# NESv4.net
KiCad netlist of a schematic drawn in EAGLE
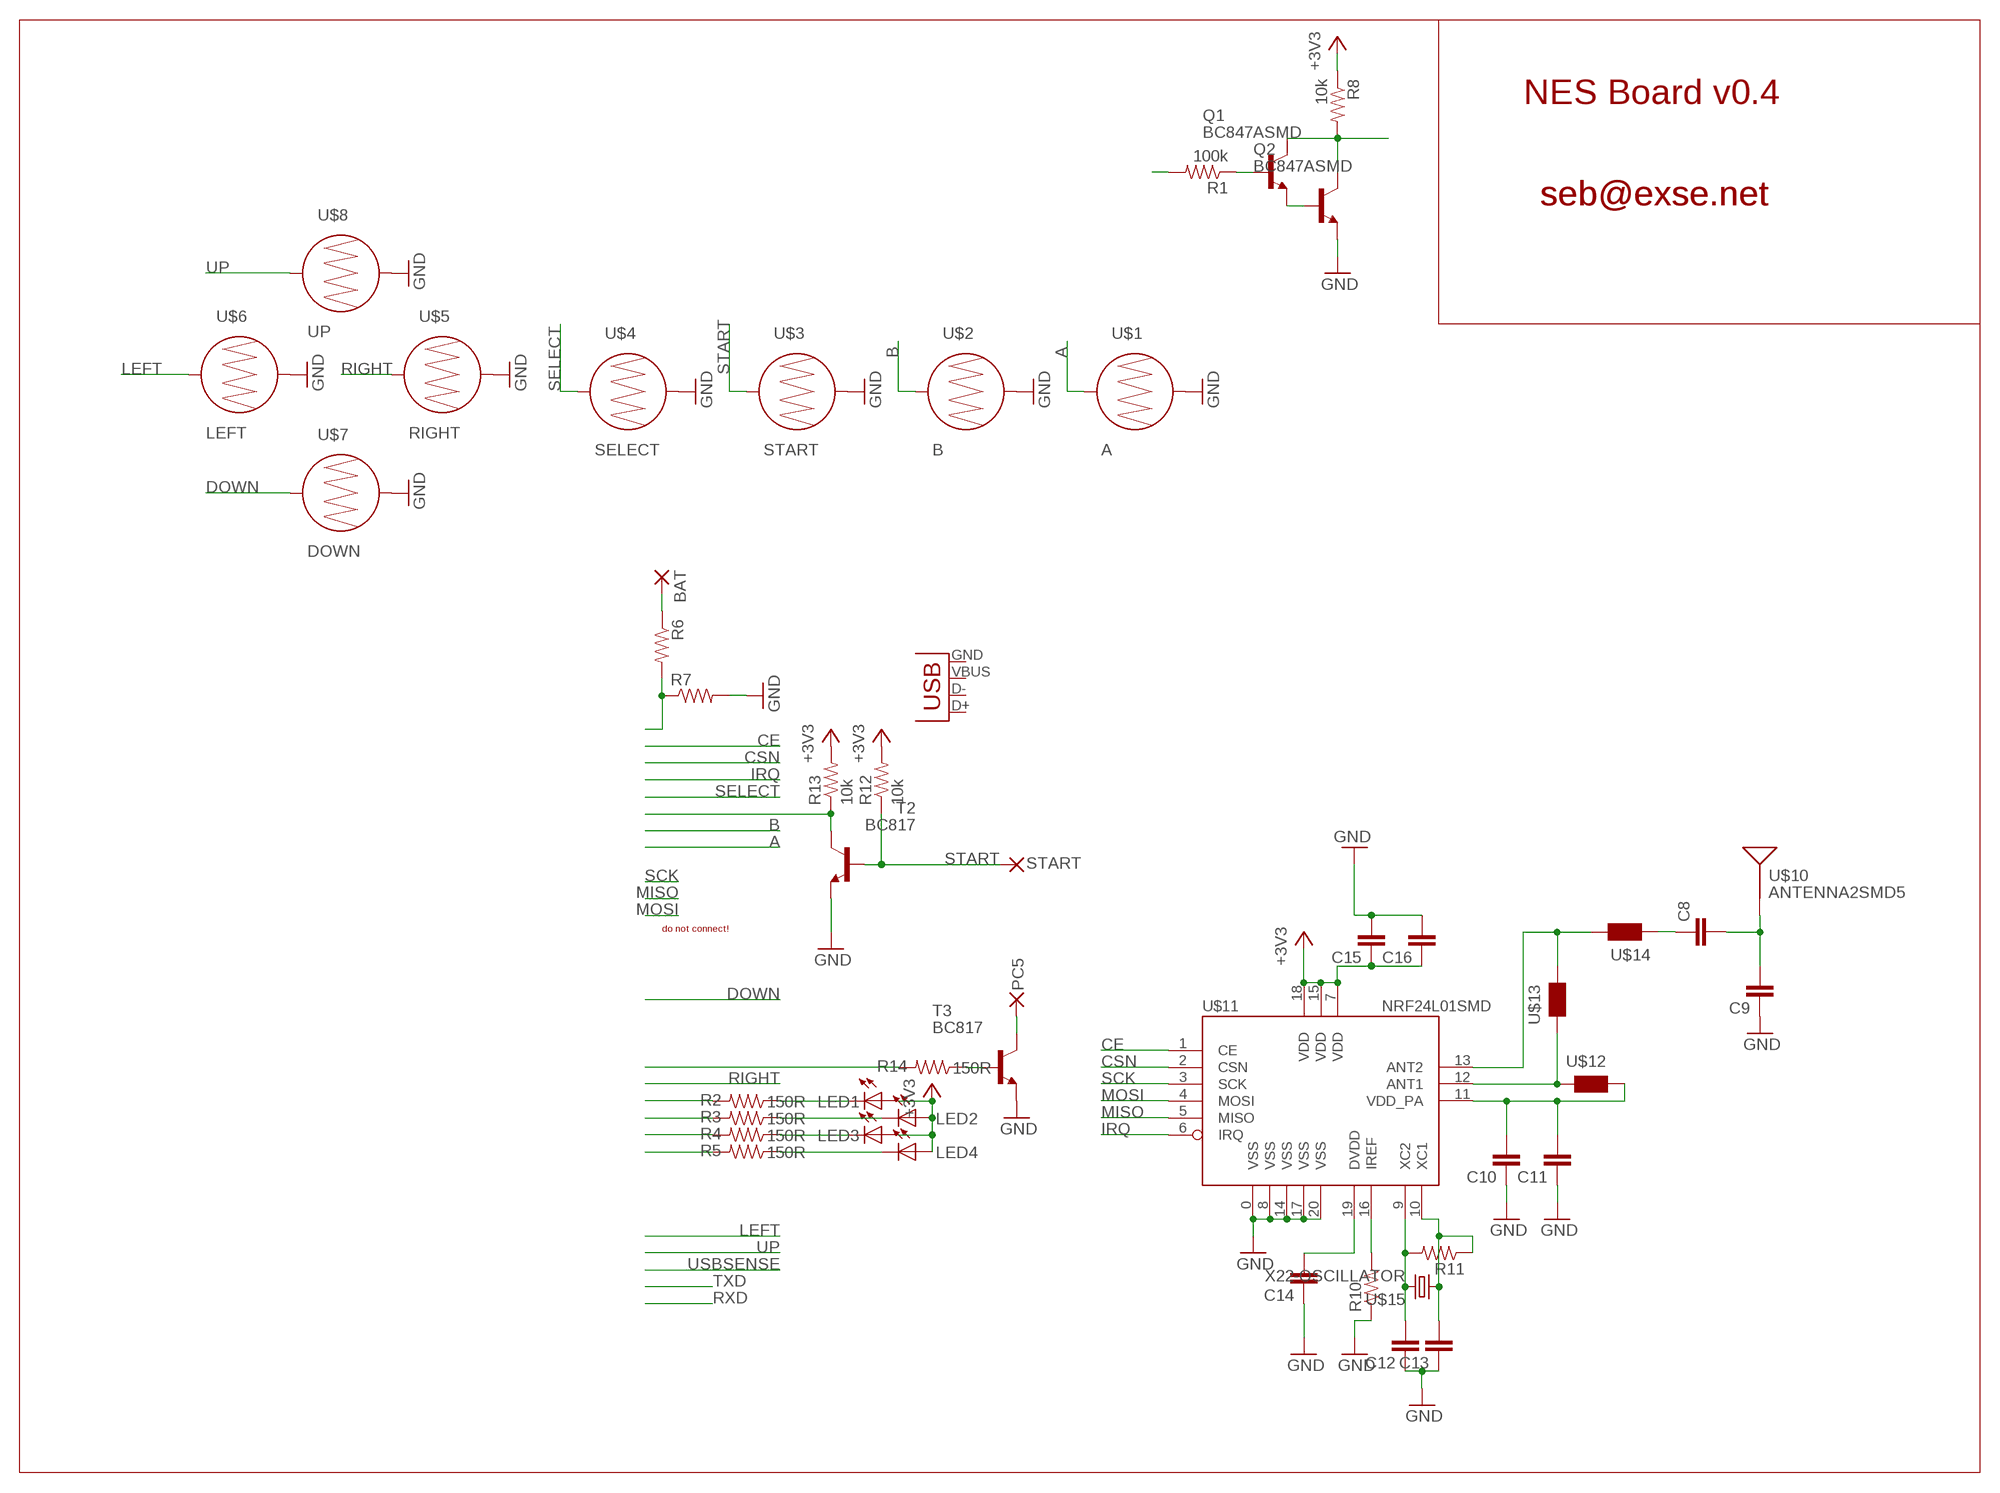
[diagram p0: schematic, sheet 1]

(export (version "E")
  (design (tool "Eeschema 10.0.6"))
  (components
    (comp (ref "BAT")
      (value "SMD2")
      (footprint "eagle-import:SMD1,27-2,54")
      (libsource (lib "eagle-import") (part "SMD2"))
    )
    (comp (ref "C8")
      (value "CAP0805")
      (footprint "eagle-import:0805")
      (libsource (lib "eagle-import") (part "CAP0805"))
    )
    (comp (ref "C9")
      (value "CAP0805")
      (footprint "eagle-import:0805")
      (libsource (lib "eagle-import") (part "CAP0805"))
    )
    (comp (ref "C10")
      (value "CAP0805")
      (footprint "eagle-import:0805")
      (libsource (lib "eagle-import") (part "CAP0805"))
    )
    (comp (ref "C11")
      (value "CAP0805")
      (footprint "eagle-import:0805")
      (libsource (lib "eagle-import") (part "CAP0805"))
    )
    (comp (ref "C12")
      (value "CAP0805")
      (footprint "eagle-import:0805")
      (libsource (lib "eagle-import") (part "CAP0805"))
    )
    (comp (ref "C13")
      (value "CAP0805")
      (footprint "eagle-import:0805")
      (libsource (lib "eagle-import") (part "CAP0805"))
    )
    (comp (ref "C14")
      (value "CAP0805")
      (footprint "eagle-import:0805")
      (libsource (lib "eagle-import") (part "CAP0805"))
    )
    (comp (ref "C15")
      (value "CAP0805")
      (footprint "eagle-import:0805")
      (libsource (lib "eagle-import") (part "CAP0805"))
    )
    (comp (ref "C16")
      (value "CAP0805")
      (footprint "eagle-import:0805")
      (libsource (lib "eagle-import") (part "CAP0805"))
    )
    (comp (ref "LED1")
      (value "LED3MM")
      (footprint "eagle-import:LED3MM")
      (libsource (lib "eagle-import") (part "LED3MM"))
    )
    (comp (ref "LED2")
      (value "LED3MM")
      (footprint "eagle-import:LED3MM")
      (libsource (lib "eagle-import") (part "LED3MM"))
    )
    (comp (ref "LED3")
      (value "LED3MM")
      (footprint "eagle-import:LED3MM")
      (libsource (lib "eagle-import") (part "LED3MM"))
    )
    (comp (ref "LED4")
      (value "LED3MM")
      (footprint "eagle-import:LED3MM")
      (libsource (lib "eagle-import") (part "LED3MM"))
    )
    (comp (ref "PC5")
      (value "SMD2")
      (footprint "eagle-import:SMD1,27-2,54")
      (libsource (lib "eagle-import") (part "SMD2"))
    )
    (comp (ref "Q1")
      (value "BC847ASMD")
      (footprint "eagle-import:SOT23")
      (libsource (lib "eagle-import") (part "BC847SMDA"))
    )
    (comp (ref "Q2")
      (value "BC847ASMD")
      (footprint "eagle-import:SOT23")
      (libsource (lib "eagle-import") (part "BC847SMDA"))
    )
    (comp (ref "R1")
      (value "100k")
      (footprint "eagle-import:0805")
      (libsource (lib "eagle-import") (part "RESISTOR"))
    )
    (comp (ref "R2")
      (value "150R")
      (footprint "eagle-import:0805")
      (libsource (lib "eagle-import") (part "RESISTOR"))
    )
    (comp (ref "R3")
      (value "150R")
      (footprint "eagle-import:0805")
      (libsource (lib "eagle-import") (part "RESISTOR"))
    )
    (comp (ref "R4")
      (value "150R")
      (footprint "eagle-import:0805")
      (libsource (lib "eagle-import") (part "RESISTOR"))
    )
    (comp (ref "R5")
      (value "150R")
      (footprint "eagle-import:0805")
      (libsource (lib "eagle-import") (part "RESISTOR"))
    )
    (comp (ref "R6")
      (value "RESISTOR")
      (footprint "eagle-import:0805")
      (libsource (lib "eagle-import") (part "RESISTOR"))
    )
    (comp (ref "R7")
      (value "RESISTOR")
      (footprint "eagle-import:0805")
      (libsource (lib "eagle-import") (part "RESISTOR"))
    )
    (comp (ref "R8")
      (value "10k")
      (footprint "eagle-import:0805")
      (libsource (lib "eagle-import") (part "RESISTOR"))
    )
    (comp (ref "R10")
      (value "RESISTOR")
      (footprint "eagle-import:0805")
      (libsource (lib "eagle-import") (part "RESISTOR"))
    )
    (comp (ref "R11")
      (value "RESISTOR")
      (footprint "eagle-import:0805")
      (libsource (lib "eagle-import") (part "RESISTOR"))
    )
    (comp (ref "R12")
      (value "10k")
      (footprint "eagle-import:0805")
      (libsource (lib "eagle-import") (part "RESISTOR"))
    )
    (comp (ref "R13")
      (value "10k")
      (footprint "eagle-import:0805")
      (libsource (lib "eagle-import") (part "RESISTOR"))
    )
    (comp (ref "R14")
      (value "150R")
      (footprint "eagle-import:0805")
      (libsource (lib "eagle-import") (part "RESISTOR"))
    )
    (comp (ref "START")
      (value "SMD2")
      (footprint "eagle-import:SMD1,27-2,54")
      (libsource (lib "eagle-import") (part "SMD2"))
    )
    (comp (ref "T2")
      (value "BC817")
      (footprint "eagle-import:SOT23")
      (libsource (lib "eagle-import") (part "BC847"))
    )
    (comp (ref "T3")
      (value "BC817")
      (footprint "eagle-import:SOT23")
      (libsource (lib "eagle-import") (part "BC847"))
    )
    (comp (ref "U$1")
      (value "A")
      (footprint "eagle-import:BUTTON-CONDUCTIVE")
      (libsource (lib "eagle-import") (part "BUTTON-CONDUCTIVESMD"))
    )
    (comp (ref "U$2")
      (value "B")
      (footprint "eagle-import:BUTTON-CONDUCTIVE")
      (libsource (lib "eagle-import") (part "BUTTON-CONDUCTIVESMD"))
    )
    (comp (ref "U$3")
      (value "START")
      (footprint "eagle-import:BUTTON-CONDUCTIVE")
      (libsource (lib "eagle-import") (part "BUTTON-CONDUCTIVESMD"))
    )
    (comp (ref "U$4")
      (value "SELECT")
      (footprint "eagle-import:BUTTON-CONDUCTIVE")
      (libsource (lib "eagle-import") (part "BUTTON-CONDUCTIVESMD"))
    )
    (comp (ref "U$5")
      (value "RIGHT")
      (footprint "eagle-import:BUTTON-CONDUCTIVE")
      (libsource (lib "eagle-import") (part "BUTTON-CONDUCTIVESMD"))
    )
    (comp (ref "U$6")
      (value "LEFT")
      (footprint "eagle-import:BUTTON-CONDUCTIVE")
      (libsource (lib "eagle-import") (part "BUTTON-CONDUCTIVESMD"))
    )
    (comp (ref "U$7")
      (value "DOWN")
      (footprint "eagle-import:BUTTON-CONDUCTIVE")
      (libsource (lib "eagle-import") (part "BUTTON-CONDUCTIVESMD"))
    )
    (comp (ref "U$8")
      (value "UP")
      (footprint "eagle-import:BUTTON-CONDUCTIVE")
      (libsource (lib "eagle-import") (part "BUTTON-CONDUCTIVESMD"))
    )
    (comp (ref "U$10")
      (value "ANTENNA2SMD5")
      (footprint "eagle-import:ANTENNA-CHIP5")
      (libsource (lib "eagle-import") (part "ANTENNA2SMD5"))
    )
    (comp (ref "U$11")
      (value "NRF24L01SMD")
      (footprint "eagle-import:QFN20")
      (libsource (lib "eagle-import") (part "NRF24L01SMD"))
    )
    (comp (ref "U$12")
      (value "WE-KIHQ_0805")
      (footprint "eagle-import:WE-KI_0805_B")
      (libsource (lib "eagle-import") (part "WE-KIHQ_0805"))
    )
    (comp (ref "U$13")
      (value "WE-KIHQ_0805")
      (footprint "eagle-import:WE-KI_0805_B")
      (libsource (lib "eagle-import") (part "WE-KIHQ_0805"))
    )
    (comp (ref "U$14")
      (value "WE-KIHQ_0805")
      (footprint "eagle-import:WE-KI_0805_B")
      (libsource (lib "eagle-import") (part "WE-KIHQ_0805"))
    )
    (comp (ref "U$15")
      (value "X22-OSCILLATOR")
      (footprint "eagle-import:X22")
      (libsource (lib "eagle-import") (part "X22-OSCILLATOR"))
    )
    (comp (ref "X1")
      (value "USB-SMD-NS")
      (footprint "eagle-import:USB-MINIB-NOSTOP")
      (libsource (lib "eagle-import") (part "USB-SMD-NS"))
    )
  )
  (nets
    (net (code "1") (name "+3V3") (class "Default")
      (node (ref "C15") (pin "1") (pinfunction "1_1") (pintype "passive"))
      (node (ref "C16") (pin "1") (pinfunction "1_1") (pintype "passive"))
      (node (ref "LED1") (pin "A") (pinfunction "A_A") (pintype "passive"))
      (node (ref "LED2") (pin "A") (pinfunction "A_A") (pintype "passive"))
      (node (ref "LED3") (pin "A") (pinfunction "A_A") (pintype "passive"))
      (node (ref "LED4") (pin "A") (pinfunction "A_A") (pintype "passive"))
      (node (ref "R12") (pin "2") (pinfunction "2_2") (pintype "passive"))
      (node (ref "R13") (pin "2") (pinfunction "2_2") (pintype "passive"))
      (node (ref "R8") (pin "1") (pinfunction "1_1") (pintype "passive"))
      (node (ref "U$11") (pin "15") (pinfunction "VDD_15") (pintype "power_in"))
      (node (ref "U$11") (pin "18") (pinfunction "VDD_18") (pintype "power_in"))
      (node (ref "U$11") (pin "7") (pinfunction "VDD_7") (pintype "power_in"))
    )
    (net (code "2") (name "/A") (class "Default")
      (node (ref "U$1") (pin "1") (pinfunction "1_1") (pintype "passive"))
    )
    (net (code "3") (name "/B") (class "Default")
      (node (ref "U$2") (pin "1") (pinfunction "1_1") (pintype "passive"))
    )
    (net (code "4") (name "/CE") (class "Default")
      (node (ref "U$11") (pin "1") (pinfunction "CE_1") (pintype "input"))
    )
    (net (code "5") (name "/CSN") (class "Default")
      (node (ref "U$11") (pin "2") (pinfunction "CSN_2") (pintype "input"))
    )
    (net (code "6") (name "/DOWN") (class "Default")
      (node (ref "U$7") (pin "1") (pinfunction "1_1") (pintype "passive"))
    )
    (net (code "7") (name "/IRQ") (class "Default")
      (node (ref "U$11") (pin "6") (pinfunction "IRQ_6") (pintype "output"))
    )
    (net (code "8") (name "/LEFT") (class "Default")
      (node (ref "U$6") (pin "1") (pinfunction "1_1") (pintype "passive"))
    )
    (net (code "9") (name "/MISO") (class "Default")
      (node (ref "U$11") (pin "5") (pinfunction "MISO_5") (pintype "output"))
    )
    (net (code "10") (name "/MOSI") (class "Default")
      (node (ref "U$11") (pin "4") (pinfunction "MOSI_4") (pintype "input"))
    )
    (net (code "11") (name "/RIGHT") (class "Default")
      (node (ref "U$5") (pin "1") (pinfunction "1_1") (pintype "passive"))
    )
    (net (code "13") (name "/SCK") (class "Default")
      (node (ref "U$11") (pin "3") (pinfunction "SCK_3") (pintype "input"))
    )
    (net (code "14") (name "/SELECT") (class "Default")
      (node (ref "U$4") (pin "1") (pinfunction "1_1") (pintype "passive"))
    )
    (net (code "15") (name "/START") (class "Default")
      (node (ref "R12") (pin "1") (pinfunction "1_1") (pintype "passive"))
      (node (ref "START") (pin "1") (pinfunction "P_1") (pintype "passive"))
      (node (ref "T2") (pin "1") (pinfunction "B_1") (pintype "passive"))
      (node (ref "U$3") (pin "1") (pinfunction "1_1") (pintype "passive"))
    )
    (net (code "17") (name "/UP") (class "Default")
      (node (ref "U$8") (pin "1") (pinfunction "1_1") (pintype "passive"))
    )
    (net (code "19") (name "GND") (class "Default")
      (node (ref "C10") (pin "1") (pinfunction "1_1") (pintype "passive"))
      (node (ref "C11") (pin "1") (pinfunction "1_1") (pintype "passive"))
      (node (ref "C12") (pin "1") (pinfunction "1_1") (pintype "passive"))
      (node (ref "C13") (pin "1") (pinfunction "1_1") (pintype "passive"))
      (node (ref "C14") (pin "1") (pinfunction "1_1") (pintype "passive"))
      (node (ref "C15") (pin "2") (pinfunction "2_2") (pintype "passive"))
      (node (ref "C16") (pin "2") (pinfunction "2_2") (pintype "passive"))
      (node (ref "C9") (pin "1") (pinfunction "1_1") (pintype "passive"))
      (node (ref "Q2") (pin "2") (pinfunction "E_2") (pintype "passive"))
      (node (ref "R10") (pin "1") (pinfunction "1_1") (pintype "passive"))
      (node (ref "R7") (pin "2") (pinfunction "2_2") (pintype "passive"))
      (node (ref "T2") (pin "2") (pinfunction "E_2") (pintype "passive"))
      (node (ref "T3") (pin "2") (pinfunction "E_2") (pintype "passive"))
      (node (ref "U$1") (pin "2") (pinfunction "2_2") (pintype "passive"))
      (node (ref "U$11") (pin "0") (pinfunction "VSS_0") (pintype "power_in"))
      (node (ref "U$11") (pin "14") (pinfunction "VSS_14") (pintype "power_in"))
      (node (ref "U$11") (pin "17") (pinfunction "VSS_17") (pintype "power_in"))
      (node (ref "U$11") (pin "20") (pinfunction "VSS_20") (pintype "power_in"))
      (node (ref "U$11") (pin "8") (pinfunction "VSS_8") (pintype "power_in"))
      (node (ref "U$2") (pin "2") (pinfunction "2_2") (pintype "passive"))
      (node (ref "U$3") (pin "2") (pinfunction "2_2") (pintype "passive"))
      (node (ref "U$4") (pin "2") (pinfunction "2_2") (pintype "passive"))
      (node (ref "U$5") (pin "2") (pinfunction "2_2") (pintype "passive"))
      (node (ref "U$6") (pin "2") (pinfunction "2_2") (pintype "passive"))
      (node (ref "U$7") (pin "2") (pinfunction "2_2") (pintype "passive"))
      (node (ref "U$8") (pin "2") (pinfunction "2_2") (pintype "passive"))
    )
    (net (code "20") (name "Net-(BAT-P)") (class "Default")
      (node (ref "BAT") (pin "1") (pinfunction "P_1") (pintype "passive"))
      (node (ref "R6") (pin "1") (pinfunction "1_1") (pintype "passive"))
    )
    (net (code "21") (name "Net-(LED1-C)") (class "Default")
      (node (ref "LED1") (pin "K") (pinfunction "C_K") (pintype "passive"))
      (node (ref "R2") (pin "1") (pinfunction "1_1") (pintype "passive"))
    )
    (net (code "22") (name "Net-(LED2-C)") (class "Default")
      (node (ref "LED2") (pin "K") (pinfunction "C_K") (pintype "passive"))
      (node (ref "R3") (pin "1") (pinfunction "1_1") (pintype "passive"))
    )
    (net (code "23") (name "Net-(LED3-C)") (class "Default")
      (node (ref "LED3") (pin "K") (pinfunction "C_K") (pintype "passive"))
      (node (ref "R4") (pin "1") (pinfunction "1_1") (pintype "passive"))
    )
    (net (code "24") (name "Net-(LED4-C)") (class "Default")
      (node (ref "LED4") (pin "K") (pinfunction "C_K") (pintype "passive"))
      (node (ref "R5") (pin "1") (pinfunction "1_1") (pintype "passive"))
    )
    (net (code "25") (name "Net-(PC5-P)") (class "Default")
      (node (ref "PC5") (pin "1") (pinfunction "P_1") (pintype "passive"))
      (node (ref "T3") (pin "3") (pinfunction "C_3") (pintype "passive"))
    )
    (net (code "26") (name "Net-(Q1-B)") (class "Default")
      (node (ref "Q1") (pin "1") (pinfunction "B_1") (pintype "passive"))
      (node (ref "R1") (pin "1") (pinfunction "1_1") (pintype "passive"))
    )
    (net (code "27") (name "Net-(Q1-C)") (class "Default")
      (node (ref "Q1") (pin "3") (pinfunction "C_3") (pintype "passive"))
      (node (ref "Q2") (pin "3") (pinfunction "C_3") (pintype "passive"))
      (node (ref "R8") (pin "2") (pinfunction "2_2") (pintype "passive"))
    )
    (net (code "28") (name "Net-(Q1-E)") (class "Default")
      (node (ref "Q1") (pin "2") (pinfunction "E_2") (pintype "passive"))
      (node (ref "Q2") (pin "1") (pinfunction "B_1") (pintype "passive"))
    )
    (net (code "29") (name "Net-(R6-Pad2)") (class "Default")
      (node (ref "R6") (pin "2") (pinfunction "2_2") (pintype "passive"))
      (node (ref "R7") (pin "1") (pinfunction "1_1") (pintype "passive"))
    )
    (net (code "30") (name "Net-(T2-C)") (class "Default")
      (node (ref "R13") (pin "1") (pinfunction "1_1") (pintype "passive"))
      (node (ref "T2") (pin "3") (pinfunction "C_3") (pintype "passive"))
    )
    (net (code "31") (name "Net-(T3-B)") (class "Default")
      (node (ref "R14") (pin "1") (pinfunction "1_1") (pintype "passive"))
      (node (ref "T3") (pin "1") (pinfunction "B_1") (pintype "passive"))
    )
    (net (code "32") (name "Net-(U$10-SIGNAL)") (class "Default")
      (node (ref "C8") (pin "2") (pinfunction "2_2") (pintype "passive"))
      (node (ref "C9") (pin "2") (pinfunction "2_2") (pintype "passive"))
      (node (ref "U$10") (pin "FEED") (pinfunction "SIGNAL_FEED") (pintype "bidirectional"))
    )
    (net (code "33") (name "Net-(U$11-ANT1)") (class "Default")
      (node (ref "U$11") (pin "12") (pinfunction "ANT1_12") (pintype "output"))
      (node (ref "U$12") (pin "2") (pinfunction "1_2") (pintype "passive"))
      (node (ref "U$13") (pin "2") (pinfunction "1_2") (pintype "passive"))
    )
    (net (code "34") (name "Net-(U$11-ANT2)") (class "Default")
      (node (ref "U$11") (pin "13") (pinfunction "ANT2_13") (pintype "output"))
      (node (ref "U$13") (pin "1") (pinfunction "2_1") (pintype "passive"))
      (node (ref "U$14") (pin "1") (pinfunction "2_1") (pintype "passive"))
    )
    (net (code "35") (name "Net-(U$11-DVDD)") (class "Default")
      (node (ref "C14") (pin "2") (pinfunction "2_2") (pintype "passive"))
      (node (ref "U$11") (pin "19") (pinfunction "DVDD_19") (pintype "power_in"))
    )
    (net (code "36") (name "Net-(U$11-IREF)") (class "Default")
      (node (ref "R10") (pin "2") (pinfunction "2_2") (pintype "passive"))
      (node (ref "U$11") (pin "16") (pinfunction "IREF_16") (pintype "input"))
    )
    (net (code "37") (name "Net-(U$11-VDD_PA)") (class "Default")
      (node (ref "C10") (pin "2") (pinfunction "2_2") (pintype "passive"))
      (node (ref "C11") (pin "2") (pinfunction "2_2") (pintype "passive"))
      (node (ref "U$11") (pin "11") (pinfunction "VDD_PA_11") (pintype "power_in"))
      (node (ref "U$12") (pin "1") (pinfunction "2_1") (pintype "passive"))
    )
    (net (code "38") (name "Net-(U$11-XC1)") (class "Default")
      (node (ref "C13") (pin "2") (pinfunction "2_2") (pintype "passive"))
      (node (ref "R11") (pin "1") (pinfunction "1_1") (pintype "passive"))
      (node (ref "U$11") (pin "10") (pinfunction "XC1_10") (pintype "input"))
      (node (ref "U$15") (pin "1") (pinfunction "1_1") (pintype "passive"))
    )
    (net (code "39") (name "Net-(U$11-XC2)") (class "Default")
      (node (ref "C12") (pin "2") (pinfunction "2_2") (pintype "passive"))
      (node (ref "R11") (pin "2") (pinfunction "2_2") (pintype "passive"))
      (node (ref "U$11") (pin "9") (pinfunction "XC2_9") (pintype "input"))
      (node (ref "U$15") (pin "3") (pinfunction "2_3") (pintype "passive"))
    )
    (net (code "40") (name "Net-(U$14-1)") (class "Default")
      (node (ref "C8") (pin "1") (pinfunction "1_1") (pintype "passive"))
      (node (ref "U$14") (pin "2") (pinfunction "1_2") (pintype "passive"))
    )
    (net (code "41") (name "unconnected-(R1-Pad2)") (class "Default")
      (node (ref "R1") (pin "2") (pinfunction "2_2") (pintype "passive"))
    )
    (net (code "42") (name "unconnected-(R2-Pad2)") (class "Default")
      (node (ref "R2") (pin "2") (pinfunction "2_2") (pintype "passive"))
    )
    (net (code "43") (name "unconnected-(R3-Pad2)") (class "Default")
      (node (ref "R3") (pin "2") (pinfunction "2_2") (pintype "passive"))
    )
    (net (code "44") (name "unconnected-(R4-Pad2)") (class "Default")
      (node (ref "R4") (pin "2") (pinfunction "2_2") (pintype "passive"))
    )
    (net (code "45") (name "unconnected-(R5-Pad2)") (class "Default")
      (node (ref "R5") (pin "2") (pinfunction "2_2") (pintype "passive"))
    )
    (net (code "46") (name "unconnected-(R14-Pad2)") (class "Default")
      (node (ref "R14") (pin "2") (pinfunction "2_2") (pintype "passive"))
    )
    (net (code "47") (name "unconnected-(X1-PadD+)") (class "Default")
      (node (ref "X1") (pin "D+") (pinfunction "D+_D+") (pintype "bidirectional"))
    )
    (net (code "48") (name "unconnected-(X1-PadD-)") (class "Default")
      (node (ref "X1") (pin "D-") (pinfunction "D-_D-") (pintype "bidirectional"))
    )
    (net (code "49") (name "unconnected-(X1-PadGND)") (class "Default")
      (node (ref "X1") (pin "GND") (pinfunction "GND_GND") (pintype "bidirectional"))
    )
    (net (code "50") (name "unconnected-(X1-PadVBUS)") (class "Default")
      (node (ref "X1") (pin "VBUS") (pinfunction "VBUS_VBUS") (pintype "bidirectional"))
    )
  )
)
